# 04_GPS.net
KiCad netlist of a schematic drawn in Altium Designer
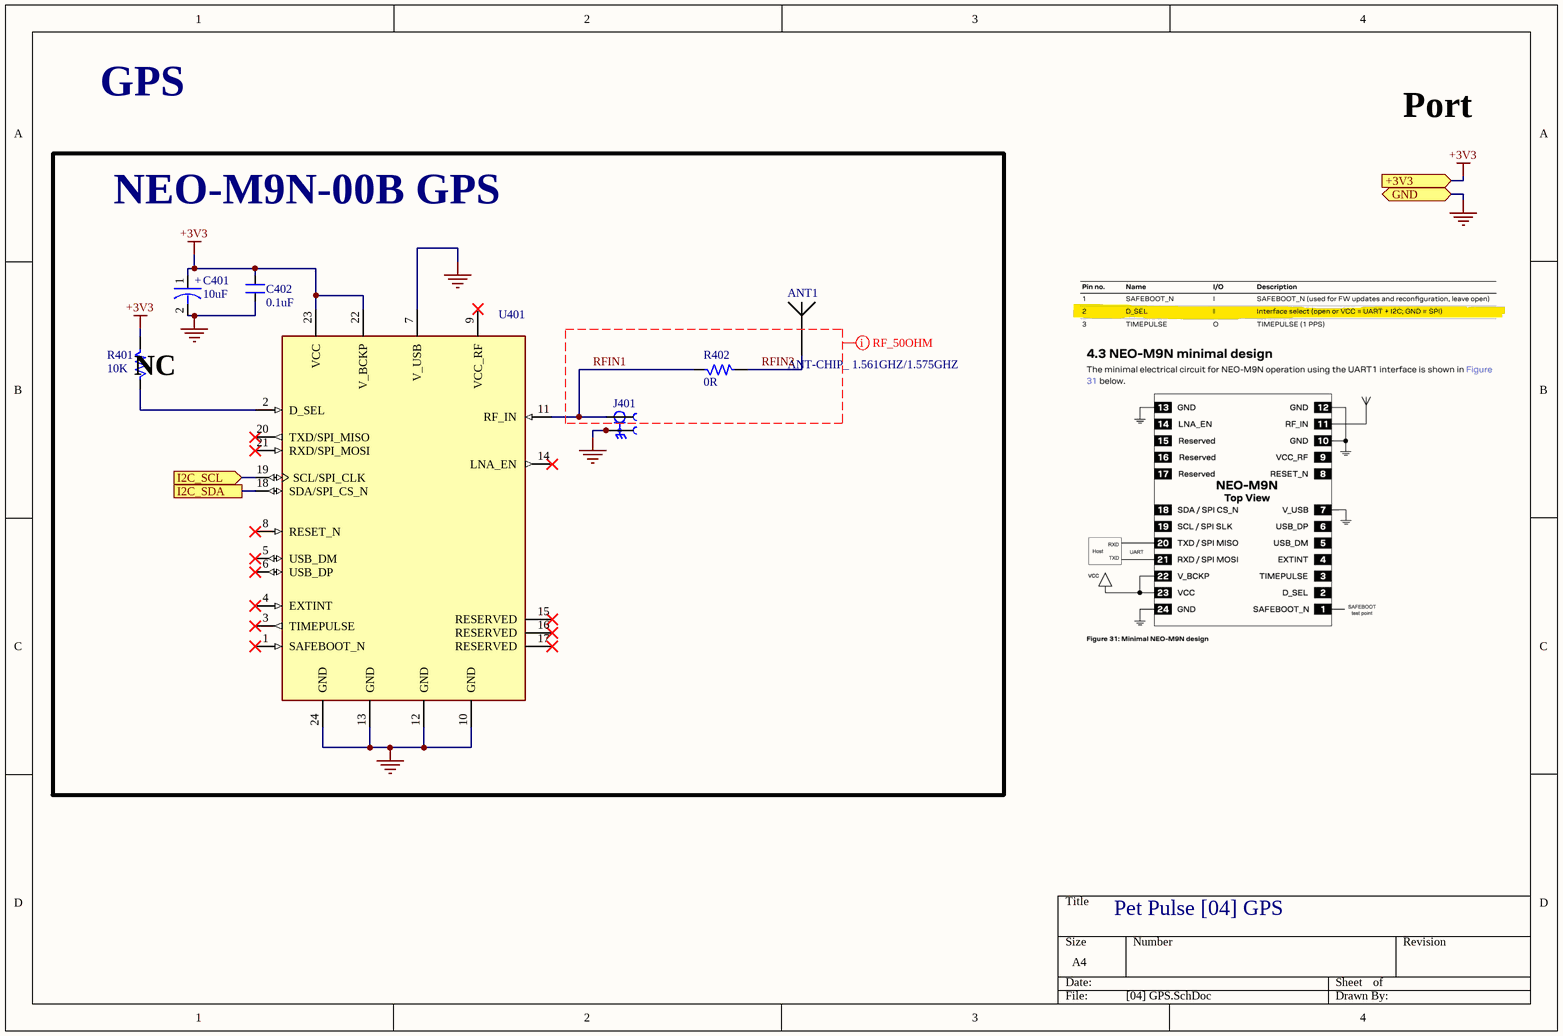
[diagram p0: [04] GPS.SchDoc]

(export (version "E")
  (design (tool "Eeschema 10.0.6"))
  (components
    (comp (ref "ANT1")
      (value "ANT-CHIP_ 1.561GHZ/1.575GHZ")
      (footprint "ANT_1575AT43A0040001E")
      (fields
        (field (name "MANUFACTURER") "Johanson Technology Inc.")
        (field (name "MANUFACTURER PART NUMBER") "1575AT43A0040E")
      )
      (libsource (lib "SchematicLibrary") (part "ANT-CHIP_ 1.561GHZ/1.575GHZ"))
    )
    (comp (ref "C401")
      (value "10uF")
      (footprint "CAP-T_1206")
      (description "10µF Molded Tantalum Capacitors 16V 1206 (3216 Metric) 3Ohm")
      (fields
        (field (name "MANUFACTURER") "AVX Corporation")
        (field (name "MANUFACTURER PART NUMBER") "TAJA106K016SNJ")
      )
      (libsource (lib "IntegratedLibraryNamanTanwar") (part "CAP-P_10uF-16V-10%-1206"))
    )
    (comp (ref "C402")
      (value "0.1uF")
      (footprint "CAP_0805")
      (description "0.1µF ±10% 50V Ceramic Capacitor X7R 0805 (2012 Metric)")
      (fields
        (field (name "MANUFACTURER") "Samsung")
        (field (name "MANUFACTURER PART NUMBER") "CL21B104KBCNNNC")
      )
      (libsource (lib "IntegratedLibraryNamanTanwar") (part "CAP_0.1uF-50V-10%-0805"))
    )
    (comp (ref "J401")
      (value "CON_UFL-SMD-T")
      (footprint "CON-UFL-SMD-T")
      (description "U.FL (UMCC) Connector Jack, Male Pin 50Ohm Surface Mount Solder")
      (fields (field (name "MP") "CONUFL001-SMD-T") (field (name "MF") "Linx"))
      (libsource (lib "IntegratedLibraryNamanTanwar") (part "CON_UFL-SMD-T"))
    )
    (comp (ref "R401")
      (value "10K")
      (footprint "RES_0805")
      (description "10 kOhms ±1% 0.125W, 1/8W Chip Resistor 0805 (2012 Metric) Automotive AEC-Q200 Thick Film")
      (fields (field (name "MANUFACTURER") "CTS") (field (name "MANUFACTURER PART NUMBER") "WR08X1002FTL"))
      (libsource (lib "IntegratedLibraryNamanTanwar") (part "RES_10K-0.125W-1%-0805"))
    )
    (comp (ref "R402")
      (value "0R")
      (footprint "RES_0603")
      (description "0 Ohms 0603 (1608 Metric)")
      (fields
        (field (name "MANUFACTURER") "Stackpole Electronics Inc")
        (field (name "MANUFACTURER PART NUMBER") "RMCF0603ZT0R00")
      )
      (libsource (lib "IntegratedLibraryNamanTanwar") (part "RES_0R-0.1W-0603"))
    )
    (comp (ref "U401")
      (value "IC_GPS/GNSS_NEO-M9N-00B")
      (footprint "IC_NEO-M9N-00B")
      (description "M9 RF Receiver BeiDou, Galileo, GLONASS, GNSS, GPS -167dBm Module")
      (fields (field (name "MANUFACTURER") "u-blox") (field (name "MANUFACTURER PART NUMBER") "NEO-M9N-00B"))
      (libsource (lib "IntegratedLibraryNamanTanwar") (part "IC_GPS/GNSS_NEO-M9N-00B"))
    )
  )
  (nets
    (net (code "1") (name "+3V3") (class "Default")
      (node (ref "C401") (pin "1") (pinfunction "1_1") (pintype "passive"))
      (node (ref "C402") (pin "2") (pinfunction "2_2") (pintype "passive"))
      (node (ref "R401") (pin "2") (pinfunction "2_2") (pintype "passive"))
      (node (ref "U401") (pin "22") (pinfunction "V_BCKP_22") (pintype "power_in"))
      (node (ref "U401") (pin "23") (pinfunction "VCC_23") (pintype "power_in"))
    )
    (net (code "2") (name "/I2C_SCL") (class "Default")
      (node (ref "U401") (pin "19") (pinfunction "SCL/SPI_CLK_19") (pintype "bidirectional"))
    )
    (net (code "3") (name "/I2C_SDA") (class "Default")
      (node (ref "U401") (pin "18") (pinfunction "SDA/SPI_CS_N_18") (pintype "bidirectional"))
    )
    (net (code "4") (name "/RFIN1") (class "Default")
      (node (ref "J401") (pin "1") (pinfunction "1_1") (pintype "passive"))
      (node (ref "R402") (pin "1") (pinfunction "1_1") (pintype "passive"))
      (node (ref "U401") (pin "11") (pinfunction "RF_IN_11") (pintype "input"))
    )
    (net (code "5") (name "/RFIN2") (class "Default")
      (node (ref "ANT1") (pin "1") (pinfunction "1_1") (pintype "passive"))
      (node (ref "R402") (pin "2") (pinfunction "2_2") (pintype "passive"))
    )
    (net (code "6") (name "GND") (class "Default")
      (node (ref "C401") (pin "2") (pinfunction "2_2") (pintype "passive"))
      (node (ref "C402") (pin "1") (pinfunction "1_1") (pintype "passive"))
      (node (ref "J401") (pin "2") (pinfunction "2_2") (pintype "passive"))
      (node (ref "J401") (pin "3") (pinfunction "2_3") (pintype "passive"))
      (node (ref "U401") (pin "10") (pinfunction "GND_10") (pintype "power_in"))
      (node (ref "U401") (pin "12") (pinfunction "GND_12") (pintype "power_in"))
      (node (ref "U401") (pin "13") (pinfunction "GND_13") (pintype "power_in"))
      (node (ref "U401") (pin "24") (pinfunction "GND_24") (pintype "power_in"))
      (node (ref "U401") (pin "7") (pinfunction "V_USB_7") (pintype "power_in"))
    )
    (net (code "7") (name "Net-(U401-D_SEL)") (class "Default")
      (node (ref "R401") (pin "1") (pinfunction "1_1") (pintype "passive"))
      (node (ref "U401") (pin "2") (pinfunction "D_SEL_2") (pintype "input"))
    )
    (net (code "8") (name "unconnected-(U401-EXTINT-Pad4)") (class "Default")
      (node (ref "U401") (pin "4") (pinfunction "EXTINT_4") (pintype "input+no_connect"))
    )
    (net (code "9") (name "unconnected-(U401-LNA_EN-Pad14)") (class "Default")
      (node (ref "U401") (pin "14") (pinfunction "LNA_EN_14") (pintype "output+no_connect"))
    )
    (net (code "10") (name "unconnected-(U401-RESERVED-Pad15)") (class "Default")
      (node (ref "U401") (pin "15") (pinfunction "RESERVED_15") (pintype "passive+no_connect"))
    )
    (net (code "11") (name "unconnected-(U401-RESERVED-Pad16)") (class "Default")
      (node (ref "U401") (pin "16") (pinfunction "RESERVED_16") (pintype "passive+no_connect"))
    )
    (net (code "12") (name "unconnected-(U401-RESERVED-Pad17)") (class "Default")
      (node (ref "U401") (pin "17") (pinfunction "RESERVED_17") (pintype "passive+no_connect"))
    )
    (net (code "13") (name "unconnected-(U401-RESET_N-Pad8)") (class "Default")
      (node (ref "U401") (pin "8") (pinfunction "RESET_N_8") (pintype "input+no_connect"))
    )
    (net (code "14") (name "unconnected-(U401-RXD{slash}SPI_MOSI-Pad21)") (class "Default")
      (node (ref "U401") (pin "21") (pinfunction "RXD/SPI_MOSI_21") (pintype "input+no_connect"))
    )
    (net (code "15") (name "unconnected-(U401-SAFEBOOT_N-Pad1)") (class "Default")
      (node (ref "U401") (pin "1") (pinfunction "SAFEBOOT_N_1") (pintype "input+no_connect"))
    )
    (net (code "16") (name "unconnected-(U401-TIMEPULSE-Pad3)") (class "Default")
      (node (ref "U401") (pin "3") (pinfunction "TIMEPULSE_3") (pintype "output+no_connect"))
    )
    (net (code "17") (name "unconnected-(U401-TXD{slash}SPI_MISO-Pad20)") (class "Default")
      (node (ref "U401") (pin "20") (pinfunction "TXD/SPI_MISO_20") (pintype "output+no_connect"))
    )
    (net (code "18") (name "unconnected-(U401-USB_DM-Pad5)") (class "Default")
      (node (ref "U401") (pin "5") (pinfunction "USB_DM_5") (pintype "bidirectional+no_connect"))
    )
    (net (code "19") (name "unconnected-(U401-USB_DP-Pad6)") (class "Default")
      (node (ref "U401") (pin "6") (pinfunction "USB_DP_6") (pintype "bidirectional+no_connect"))
    )
    (net (code "20") (name "unconnected-(U401-VCC_RF-Pad9)") (class "Default")
      (node (ref "U401") (pin "9") (pinfunction "VCC_RF_9") (pintype "power_in+no_connect"))
    )
  )
)
